# GlassesSync_TOP.net
KiCad netlist of a schematic drawn in Altium Designer
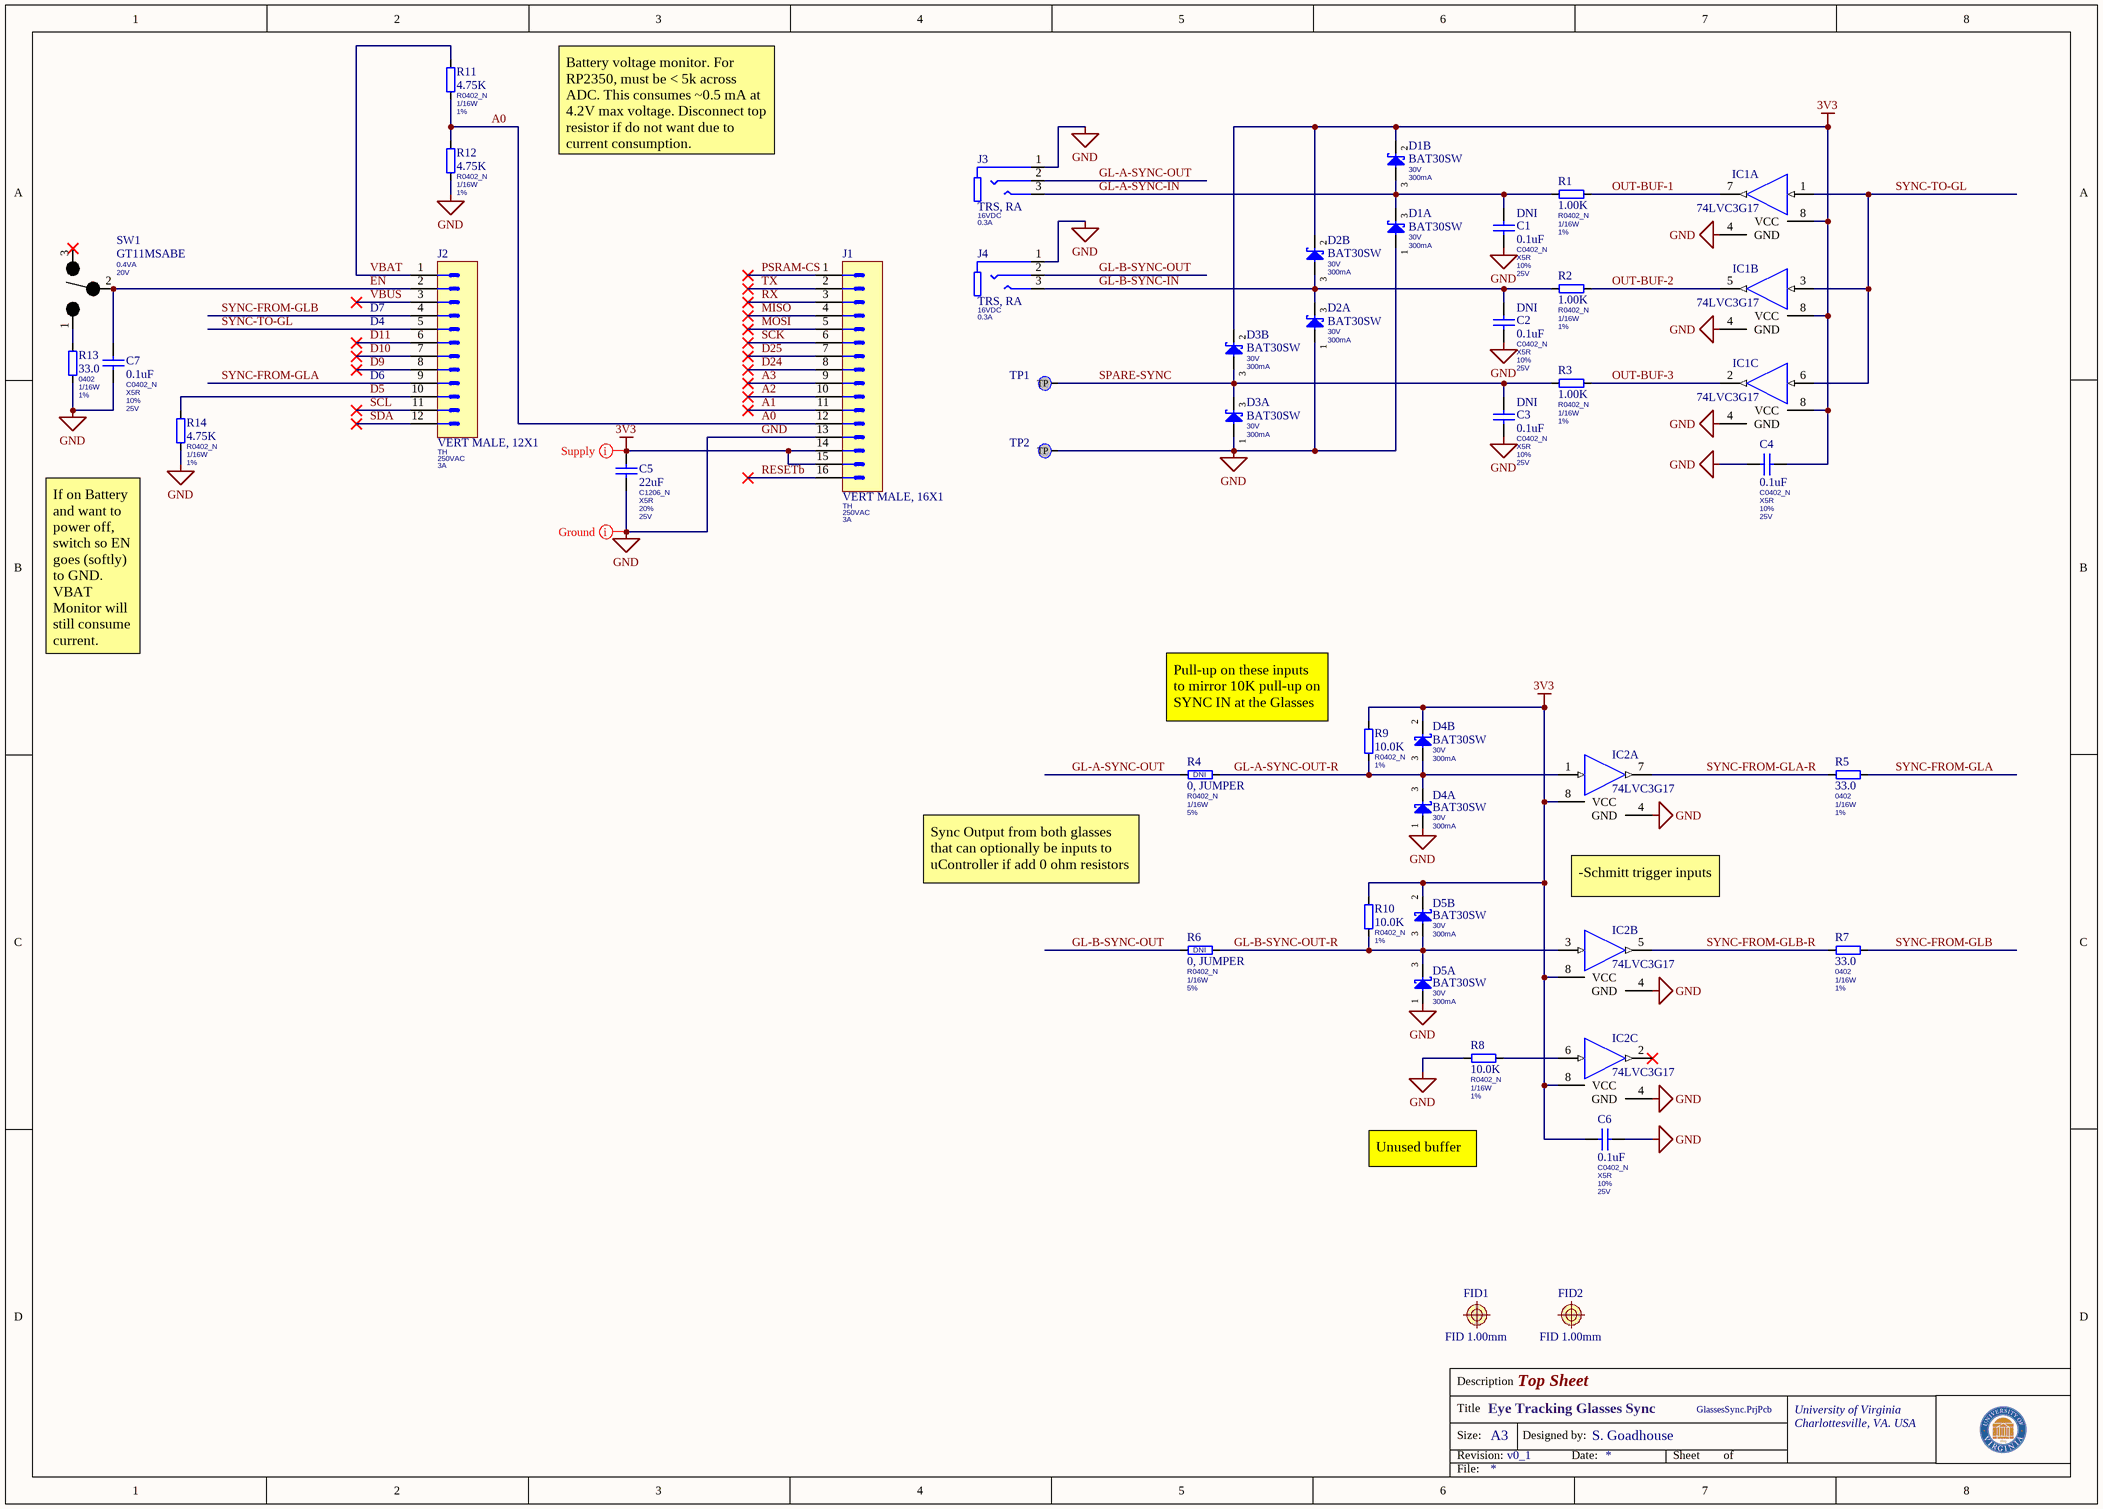
[diagram p0: GlassesSync_TOP.SchDoc]

(export (version "E")
  (design (tool "Eeschema 10.0.6"))
  (components
    (comp (ref "C1")
      (value "0.1uF")
      (footprint "C0402_N")
      (description "Capacitor")
      (fields
        (field (name "TC") "X5R")
        (field (name "TOLERANCE") "10%")
        (field (name "VOLTAGE") "25V")
        (field (name "PLACE") "DNI")
      )
      (libsource (lib "Local_Components") (part "Cap"))
    )
    (comp (ref "C2")
      (value "0.1uF")
      (footprint "C0402_N")
      (description "Capacitor")
      (fields
        (field (name "TC") "X5R")
        (field (name "TOLERANCE") "10%")
        (field (name "VOLTAGE") "25V")
        (field (name "PLACE") "DNI")
      )
      (libsource (lib "Local_Components") (part "Cap"))
    )
    (comp (ref "C3")
      (value "0.1uF")
      (footprint "C0402_N")
      (description "Capacitor")
      (fields
        (field (name "TC") "X5R")
        (field (name "TOLERANCE") "10%")
        (field (name "VOLTAGE") "25V")
        (field (name "PLACE") "DNI")
      )
      (libsource (lib "Local_Components") (part "Cap"))
    )
    (comp (ref "C4")
      (value "0.1uF")
      (footprint "C0402_N")
      (description "Capacitor")
      (fields (field (name "TC") "X5R") (field (name "TOLERANCE") "10%") (field (name "VOLTAGE") "25V"))
      (libsource (lib "Local_Components") (part "Cap"))
    )
    (comp (ref "C5")
      (value "22uF")
      (footprint "C1206_N")
      (description "Capacitor")
      (fields (field (name "TC") "X5R") (field (name "TOLERANCE") "20%") (field (name "VOLTAGE") "25V"))
      (libsource (lib "Local_Components") (part "Cap"))
    )
    (comp (ref "C6")
      (value "0.1uF")
      (footprint "C0402_N")
      (description "Capacitor")
      (fields (field (name "TC") "X5R") (field (name "TOLERANCE") "10%") (field (name "VOLTAGE") "25V"))
      (libsource (lib "Local_Components") (part "Cap"))
    )
    (comp (ref "C7")
      (value "0.1uF")
      (footprint "C0402_N")
      (description "Capacitor")
      (fields (field (name "TC") "X5R") (field (name "TOLERANCE") "10%") (field (name "VOLTAGE") "25V"))
      (libsource (lib "Local_Components") (part "Cap"))
    )
    (comp (ref "D1")
      (value "BAT30SW")
      (footprint "SOT65P210X110-3_N")
      (description "Serial Schottky Diode")
      (fields (field (name "VOLTAGE") "30V") (field (name "CURRENT") "300mA") (field (name "POWER") "225mW"))
      (libsource (lib "Local_Components") (part "Diode Schottky x2 A1C3_A3C2"))
    )
    (comp (ref "D2")
      (value "BAT30SW")
      (footprint "SOT65P210X110-3_N")
      (description "Serial Schottky Diode")
      (fields (field (name "VOLTAGE") "30V") (field (name "CURRENT") "300mA") (field (name "POWER") "225mW"))
      (libsource (lib "Local_Components") (part "Diode Schottky x2 A1C3_A3C2"))
    )
    (comp (ref "D3")
      (value "BAT30SW")
      (footprint "SOT65P210X110-3_N")
      (description "Serial Schottky Diode")
      (fields (field (name "VOLTAGE") "30V") (field (name "CURRENT") "300mA") (field (name "POWER") "225mW"))
      (libsource (lib "Local_Components") (part "Diode Schottky x2 A1C3_A3C2"))
    )
    (comp (ref "D4")
      (value "BAT30SW")
      (footprint "SOT65P210X110-3_N")
      (description "Serial Schottky Diode")
      (fields (field (name "VOLTAGE") "30V") (field (name "CURRENT") "300mA") (field (name "POWER") "225mW"))
      (libsource (lib "Local_Components") (part "Diode Schottky x2 A1C3_A3C2"))
    )
    (comp (ref "D5")
      (value "BAT30SW")
      (footprint "SOT65P210X110-3_N")
      (description "Serial Schottky Diode")
      (fields (field (name "VOLTAGE") "30V") (field (name "CURRENT") "300mA") (field (name "POWER") "225mW"))
      (libsource (lib "Local_Components") (part "Diode Schottky x2 A1C3_A3C2"))
    )
    (comp (ref "FID1")
      (value "FID 1.00mm")
      (footprint "FIDUCIAL_C100-200-250")
      (description "Fiducial for PCB registration")
      (libsource (lib "Local_Components") (part "FIDUCIAL"))
    )
    (comp (ref "FID2")
      (value "FID 1.00mm")
      (footprint "FIDUCIAL_C100-200-250")
      (description "Fiducial for PCB registration")
      (libsource (lib "Local_Components") (part "FIDUCIAL"))
    )
    (comp (ref "IC1")
      (value "74LVC3G17")
      (footprint "SOP50P310X90-8_N")
      (description "Triple Schmitt-Trigger Non-Inverter Buffers")
      (fields (field (name "VOLTAGE") "1.65-5.5V"))
      (libsource (lib "Local_Components") (part "7417-3G"))
    )
    (comp (ref "IC2")
      (value "74LVC3G17")
      (footprint "SOP50P310X90-8_N")
      (description "Triple Schmitt-Trigger Non-Inverter Buffers")
      (fields (field (name "VOLTAGE") "1.65-5.5V"))
      (libsource (lib "Local_Components") (part "7417-3G"))
    )
    (comp (ref "J1")
      (value "VERT MALE, 16X1")
      (footprint "TH-CONN16A-HDR")
      (description "Male pin header 16x1")
      (fields (field (name "CASE") "TH") (field (name "VOLTAGE") "250VAC") (field (name "CURRENT") "3A"))
      (libsource (lib "Local_Components") (part "HEADER-16X1"))
    )
    (comp (ref "J2")
      (value "VERT MALE, 12X1")
      (footprint "TH-CONN12B-HDR")
      (description "Male pin header 12x1")
      (fields (field (name "CASE") "TH") (field (name "VOLTAGE") "250VAC") (field (name "CURRENT") "3A"))
      (libsource (lib "Local_Components") (part "HEADER-12X1"))
    )
    (comp (ref "J3")
      (value "TRS, RA")
      (footprint "TH-CONN3A-TRS")
      (fields (field (name "CURRENT") "0.3A") (field (name "VOLTAGE") "16VDC"))
      (libsource (lib "Local_Components") (part "CONN-TRS-3PIN-A"))
    )
    (comp (ref "J4")
      (value "TRS, RA")
      (footprint "TH-CONN3A-TRS")
      (fields (field (name "CURRENT") "0.3A") (field (name "VOLTAGE") "16VDC"))
      (libsource (lib "Local_Components") (part "CONN-TRS-3PIN-A"))
    )
    (comp (ref "R1")
      (value "1.00K")
      (footprint "R0402_N")
      (description "Resistor")
      (fields (field (name "POWER") "1/16W") (field (name "TOLERANCE") "1%"))
      (libsource (lib "Local_Components") (part "Res"))
    )
    (comp (ref "R2")
      (value "1.00K")
      (footprint "R0402_N")
      (description "Resistor")
      (fields (field (name "POWER") "1/16W") (field (name "TOLERANCE") "1%"))
      (libsource (lib "Local_Components") (part "Res"))
    )
    (comp (ref "R3")
      (value "1.00K")
      (footprint "R0402_N")
      (description "Resistor")
      (fields (field (name "POWER") "1/16W") (field (name "TOLERANCE") "1%"))
      (libsource (lib "Local_Components") (part "Res"))
    )
    (comp (ref "R4")
      (value "0, JUMPER")
      (footprint "R0402_N")
      (description "Resistor")
      (fields (field (name "POWER") "1/16W") (field (name "TOLERANCE") "5%") (field (name "PLACE") "DNI"))
      (libsource (lib "Local_Components") (part "Res"))
    )
    (comp (ref "R5")
      (value "33.0")
      (footprint "R0402_N")
      (description "Resistor")
      (fields (field (name "CASE") "0402") (field (name "POWER") "1/16W") (field (name "TOLERANCE") "1%"))
      (libsource (lib "Local_Components") (part "Res"))
    )
    (comp (ref "R6")
      (value "0, JUMPER")
      (footprint "R0402_N")
      (description "Resistor")
      (fields (field (name "POWER") "1/16W") (field (name "TOLERANCE") "5%") (field (name "PLACE") "DNI"))
      (libsource (lib "Local_Components") (part "Res"))
    )
    (comp (ref "R7")
      (value "33.0")
      (footprint "R0402_N")
      (description "Resistor")
      (fields (field (name "CASE") "0402") (field (name "POWER") "1/16W") (field (name "TOLERANCE") "1%"))
      (libsource (lib "Local_Components") (part "Res"))
    )
    (comp (ref "R8")
      (value "10.0K")
      (footprint "R0402_N")
      (description "Resistor")
      (fields (field (name "POWER") "1/16W") (field (name "TOLERANCE") "1%"))
      (libsource (lib "Local_Components") (part "Res"))
    )
    (comp (ref "R9")
      (value "10.0K")
      (footprint "R0402_N")
      (description "Resistor")
      (fields (field (name "POWER") "1/16W") (field (name "TOLERANCE") "1%"))
      (libsource (lib "Local_Components") (part "Res"))
    )
    (comp (ref "R10")
      (value "10.0K")
      (footprint "R0402_N")
      (description "Resistor")
      (fields (field (name "POWER") "1/16W") (field (name "TOLERANCE") "1%"))
      (libsource (lib "Local_Components") (part "Res"))
    )
    (comp (ref "R11")
      (value "4.75K")
      (footprint "R0402_N")
      (description "Resistor")
      (fields (field (name "POWER") "1/16W") (field (name "TOLERANCE") "1%"))
      (libsource (lib "Local_Components") (part "Res"))
    )
    (comp (ref "R12")
      (value "4.75K")
      (footprint "R0402_N")
      (description "Resistor")
      (fields (field (name "POWER") "1/16W") (field (name "TOLERANCE") "1%"))
      (libsource (lib "Local_Components") (part "Res"))
    )
    (comp (ref "R13")
      (value "33.0")
      (footprint "R0402_N")
      (description "Resistor")
      (fields (field (name "CASE") "0402") (field (name "POWER") "1/16W") (field (name "TOLERANCE") "1%"))
      (libsource (lib "Local_Components") (part "Res"))
    )
    (comp (ref "R14")
      (value "4.75K")
      (footprint "R0402_N")
      (description "Resistor")
      (fields (field (name "POWER") "1/16W") (field (name "TOLERANCE") "1%"))
      (libsource (lib "Local_Components") (part "Res"))
    )
    (comp (ref "SW1")
      (value "GT11MSABE")
      (footprint "GT13MSABE")
      (description "Switch Toggle, SPDT")
      (fields (field (name "CURRENT") "0.4VA") (field (name "VOLTAGE") "20V"))
      (libsource (lib "Local_Components") (part "SWITCH-SPDT-B"))
    )
    (comp (ref "TP1")
      (value "TP")
      (footprint "TPAD-SQ")
      (description "Test Point")
      (libsource (lib "Components") (part "TP"))
    )
    (comp (ref "TP2")
      (value "TP")
      (footprint "TPAD-SQ")
      (description "Test Point")
      (libsource (lib "Components") (part "TP"))
    )
  )
  (nets
    (net (code "1") (name "/A0") (class "Default")
      (node (ref "J1") (pin "12") (pinfunction "12_12") (pintype "passive"))
      (node (ref "R11") (pin "1") (pinfunction "1_1") (pintype "passive"))
      (node (ref "R12") (pin "2") (pinfunction "2_2") (pintype "passive"))
    )
    (net (code "2") (name "/A1") (class "Default")
      (node (ref "J1") (pin "11") (pinfunction "11_11") (pintype "passive+no_connect"))
    )
    (net (code "3") (name "/A2") (class "Default")
      (node (ref "J1") (pin "10") (pinfunction "10_10") (pintype "passive+no_connect"))
    )
    (net (code "4") (name "/A3") (class "Default")
      (node (ref "J1") (pin "9") (pinfunction "9_9") (pintype "passive+no_connect"))
    )
    (net (code "5") (name "/D5") (class "Default")
      (node (ref "J2") (pin "10") (pinfunction "10_10") (pintype "passive"))
      (node (ref "R14") (pin "2") (pinfunction "2_2") (pintype "passive"))
    )
    (net (code "6") (name "/D9") (class "Default")
      (node (ref "J2") (pin "8") (pinfunction "8_8") (pintype "passive+no_connect"))
    )
    (net (code "7") (name "/D10") (class "Default")
      (node (ref "J2") (pin "7") (pinfunction "7_7") (pintype "passive+no_connect"))
    )
    (net (code "8") (name "/D11") (class "Default")
      (node (ref "J2") (pin "6") (pinfunction "6_6") (pintype "passive+no_connect"))
    )
    (net (code "9") (name "/D24") (class "Default")
      (node (ref "J1") (pin "8") (pinfunction "8_8") (pintype "passive+no_connect"))
    )
    (net (code "10") (name "/D25") (class "Default")
      (node (ref "J1") (pin "7") (pinfunction "7_7") (pintype "passive+no_connect"))
    )
    (net (code "11") (name "/EN") (class "Default")
      (node (ref "C7") (pin "2") (pinfunction "2_2") (pintype "passive"))
      (node (ref "J2") (pin "2") (pinfunction "2_2") (pintype "passive"))
      (node (ref "SW1") (pin "2") (pinfunction "2_2") (pintype "passive"))
    )
    (net (code "12") (name "/GL-A-SYNC-IN") (class "Default")
      (node (ref "C1") (pin "1") (pinfunction "1_1") (pintype "passive"))
      (node (ref "D1") (pin "3") (pinfunction "COMAC_3") (pintype "passive"))
      (node (ref "J3") (pin "3") (pinfunction "3_3") (pintype "passive"))
      (node (ref "R1") (pin "2") (pinfunction "2_2") (pintype "passive"))
    )
    (net (code "13") (name "/GL-A-SYNC-OUT") (class "Default")
      (node (ref "J3") (pin "2") (pinfunction "2_2") (pintype "passive"))
      (node (ref "R4") (pin "2") (pinfunction "2_2") (pintype "passive"))
    )
    (net (code "14") (name "/GL-A-SYNC-OUT-R") (class "Default")
      (node (ref "D4") (pin "3") (pinfunction "COMAC_3") (pintype "passive"))
      (node (ref "IC2") (pin "1") (pinfunction "IN1_1") (pintype "input"))
      (node (ref "R4") (pin "1") (pinfunction "1_1") (pintype "passive"))
      (node (ref "R9") (pin "1") (pinfunction "1_1") (pintype "passive"))
    )
    (net (code "15") (name "/GL-B-SYNC-IN") (class "Default")
      (node (ref "C2") (pin "1") (pinfunction "1_1") (pintype "passive"))
      (node (ref "D2") (pin "3") (pinfunction "COMAC_3") (pintype "passive"))
      (node (ref "J4") (pin "3") (pinfunction "3_3") (pintype "passive"))
      (node (ref "R2") (pin "2") (pinfunction "2_2") (pintype "passive"))
    )
    (net (code "16") (name "/GL-B-SYNC-OUT") (class "Default")
      (node (ref "J4") (pin "2") (pinfunction "2_2") (pintype "passive"))
      (node (ref "R6") (pin "2") (pinfunction "2_2") (pintype "passive"))
    )
    (net (code "17") (name "/GL-B-SYNC-OUT-R") (class "Default")
      (node (ref "D5") (pin "3") (pinfunction "COMAC_3") (pintype "passive"))
      (node (ref "IC2") (pin "3") (pinfunction "IN2_3") (pintype "input"))
      (node (ref "R10") (pin "1") (pinfunction "1_1") (pintype "passive"))
      (node (ref "R6") (pin "1") (pinfunction "1_1") (pintype "passive"))
    )
    (net (code "18") (name "/MISO") (class "Default")
      (node (ref "J1") (pin "4") (pinfunction "4_4") (pintype "passive+no_connect"))
    )
    (net (code "19") (name "/MOSI") (class "Default")
      (node (ref "J1") (pin "5") (pinfunction "5_5") (pintype "passive+no_connect"))
    )
    (net (code "20") (name "/OUT-BUF-1") (class "Default")
      (node (ref "IC1") (pin "7") (pinfunction "OUT1_7") (pintype "output"))
      (node (ref "R1") (pin "1") (pinfunction "1_1") (pintype "passive"))
    )
    (net (code "21") (name "/OUT-BUF-2") (class "Default")
      (node (ref "IC1") (pin "5") (pinfunction "OUT2_5") (pintype "output"))
      (node (ref "R2") (pin "1") (pinfunction "1_1") (pintype "passive"))
    )
    (net (code "22") (name "/OUT-BUF-3") (class "Default")
      (node (ref "IC1") (pin "2") (pinfunction "OUT3_2") (pintype "output"))
      (node (ref "R3") (pin "1") (pinfunction "1_1") (pintype "passive"))
    )
    (net (code "23") (name "/PSRAM-CS") (class "Default")
      (node (ref "J1") (pin "1") (pinfunction "1_1") (pintype "passive+no_connect"))
    )
    (net (code "24") (name "/RESETb") (class "Default")
      (node (ref "J1") (pin "16") (pinfunction "16_16") (pintype "passive+no_connect"))
    )
    (net (code "25") (name "/RX") (class "Default")
      (node (ref "J1") (pin "3") (pinfunction "3_3") (pintype "passive+no_connect"))
    )
    (net (code "26") (name "/SCK") (class "Default")
      (node (ref "J1") (pin "6") (pinfunction "6_6") (pintype "passive+no_connect"))
    )
    (net (code "27") (name "/SCL") (class "Default")
      (node (ref "J2") (pin "11") (pinfunction "11_11") (pintype "passive+no_connect"))
    )
    (net (code "28") (name "/SDA") (class "Default")
      (node (ref "J2") (pin "12") (pinfunction "12_12") (pintype "passive+no_connect"))
    )
    (net (code "29") (name "/SPARE-SYNC") (class "Default")
      (node (ref "C3") (pin "1") (pinfunction "1_1") (pintype "passive"))
      (node (ref "D3") (pin "3") (pinfunction "COMAC_3") (pintype "passive"))
      (node (ref "R3") (pin "2") (pinfunction "2_2") (pintype "passive"))
      (node (ref "TP1") (pin "1") (pinfunction "TP_1") (pintype "passive"))
    )
    (net (code "30") (name "/SYNC-FROM-GLA") (class "Default")
      (node (ref "J2") (pin "9") (pinfunction "9_9") (pintype "passive"))
      (node (ref "R5") (pin "1") (pinfunction "1_1") (pintype "passive"))
    )
    (net (code "31") (name "/SYNC-FROM-GLA-R") (class "Default")
      (node (ref "IC2") (pin "7") (pinfunction "OUT1_7") (pintype "output"))
      (node (ref "R5") (pin "2") (pinfunction "2_2") (pintype "passive"))
    )
    (net (code "32") (name "/SYNC-FROM-GLB") (class "Default")
      (node (ref "J2") (pin "4") (pinfunction "4_4") (pintype "passive"))
      (node (ref "R7") (pin "1") (pinfunction "1_1") (pintype "passive"))
    )
    (net (code "33") (name "/SYNC-FROM-GLB-R") (class "Default")
      (node (ref "IC2") (pin "5") (pinfunction "OUT2_5") (pintype "output"))
      (node (ref "R7") (pin "2") (pinfunction "2_2") (pintype "passive"))
    )
    (net (code "34") (name "/SYNC-TO-GL") (class "Default")
      (node (ref "IC1") (pin "1") (pinfunction "IN1_1") (pintype "input"))
      (node (ref "IC1") (pin "3") (pinfunction "IN2_3") (pintype "input"))
      (node (ref "IC1") (pin "6") (pinfunction "IN3_6") (pintype "input"))
      (node (ref "J2") (pin "5") (pinfunction "5_5") (pintype "passive"))
    )
    (net (code "35") (name "/TX") (class "Default")
      (node (ref "J1") (pin "2") (pinfunction "2_2") (pintype "passive+no_connect"))
    )
    (net (code "36") (name "/VBAT") (class "Default")
      (node (ref "J2") (pin "1") (pinfunction "1_1") (pintype "passive"))
      (node (ref "R11") (pin "2") (pinfunction "2_2") (pintype "passive"))
    )
    (net (code "37") (name "/VBUS") (class "Default")
      (node (ref "J2") (pin "3") (pinfunction "3_3") (pintype "passive+no_connect"))
    )
    (net (code "38") (name "3V3") (class "Default")
      (node (ref "C4") (pin "1") (pinfunction "1_1") (pintype "passive"))
      (node (ref "C5") (pin "1") (pinfunction "1_1") (pintype "passive"))
      (node (ref "C6") (pin "2") (pinfunction "2_2") (pintype "passive"))
      (node (ref "D1") (pin "2") (pinfunction "C_2") (pintype "passive"))
      (node (ref "D2") (pin "2") (pinfunction "C_2") (pintype "passive"))
      (node (ref "D3") (pin "2") (pinfunction "C_2") (pintype "passive"))
      (node (ref "D4") (pin "2") (pinfunction "C_2") (pintype "passive"))
      (node (ref "D5") (pin "2") (pinfunction "C_2") (pintype "passive"))
      (node (ref "IC1") (pin "8") (pinfunction "VCC_8") (pintype "power_in"))
      (node (ref "IC2") (pin "8") (pinfunction "VCC_8") (pintype "power_in"))
      (node (ref "J1") (pin "14") (pinfunction "14_14") (pintype "passive"))
      (node (ref "J1") (pin "15") (pinfunction "15_15") (pintype "passive"))
      (node (ref "R10") (pin "2") (pinfunction "2_2") (pintype "passive"))
      (node (ref "R9") (pin "2") (pinfunction "2_2") (pintype "passive"))
    )
    (net (code "39") (name "GND") (class "Default")
      (node (ref "C1") (pin "2") (pinfunction "2_2") (pintype "passive"))
      (node (ref "C2") (pin "2") (pinfunction "2_2") (pintype "passive"))
      (node (ref "C3") (pin "2") (pinfunction "2_2") (pintype "passive"))
      (node (ref "C4") (pin "2") (pinfunction "2_2") (pintype "passive"))
      (node (ref "C5") (pin "2") (pinfunction "2_2") (pintype "passive"))
      (node (ref "C6") (pin "1") (pinfunction "1_1") (pintype "passive"))
      (node (ref "C7") (pin "1") (pinfunction "1_1") (pintype "passive"))
      (node (ref "D1") (pin "1") (pinfunction "A_1") (pintype "passive"))
      (node (ref "D2") (pin "1") (pinfunction "A_1") (pintype "passive"))
      (node (ref "D3") (pin "1") (pinfunction "A_1") (pintype "passive"))
      (node (ref "D4") (pin "1") (pinfunction "A_1") (pintype "passive"))
      (node (ref "D5") (pin "1") (pinfunction "A_1") (pintype "passive"))
      (node (ref "IC1") (pin "4") (pinfunction "GND_4") (pintype "power_in"))
      (node (ref "IC2") (pin "4") (pinfunction "GND_4") (pintype "power_in"))
      (node (ref "J1") (pin "13") (pinfunction "13_13") (pintype "passive"))
      (node (ref "J3") (pin "1") (pinfunction "1_1") (pintype "passive"))
      (node (ref "J4") (pin "1") (pinfunction "1_1") (pintype "passive"))
      (node (ref "R12") (pin "1") (pinfunction "1_1") (pintype "passive"))
      (node (ref "R13") (pin "2") (pinfunction "2_2") (pintype "passive"))
      (node (ref "R14") (pin "1") (pinfunction "1_1") (pintype "passive"))
      (node (ref "R8") (pin "1") (pinfunction "1_1") (pintype "passive"))
      (node (ref "TP2") (pin "1") (pinfunction "TP_1") (pintype "passive"))
    )
    (net (code "40") (name "Net-(IC2C-IN3)") (class "Default")
      (node (ref "IC2") (pin "6") (pinfunction "IN3_6") (pintype "input"))
      (node (ref "R8") (pin "2") (pinfunction "2_2") (pintype "passive"))
    )
    (net (code "41") (name "Net-(R13-Pad1)") (class "Default")
      (node (ref "R13") (pin "1") (pinfunction "1_1") (pintype "passive"))
      (node (ref "SW1") (pin "1") (pinfunction "1_1") (pintype "passive"))
    )
    (net (code "42") (name "unconnected-(IC2C-OUT3-Pad2)") (class "Default")
      (node (ref "IC2") (pin "2") (pinfunction "OUT3_2") (pintype "output+no_connect"))
    )
    (net (code "43") (name "unconnected-(SW1-Pad3)") (class "Default")
      (node (ref "SW1") (pin "3") (pinfunction "3_3") (pintype "passive+no_connect"))
    )
  )
)
